# Colon.net
KiCad netlist of a schematic drawn in EAGLE
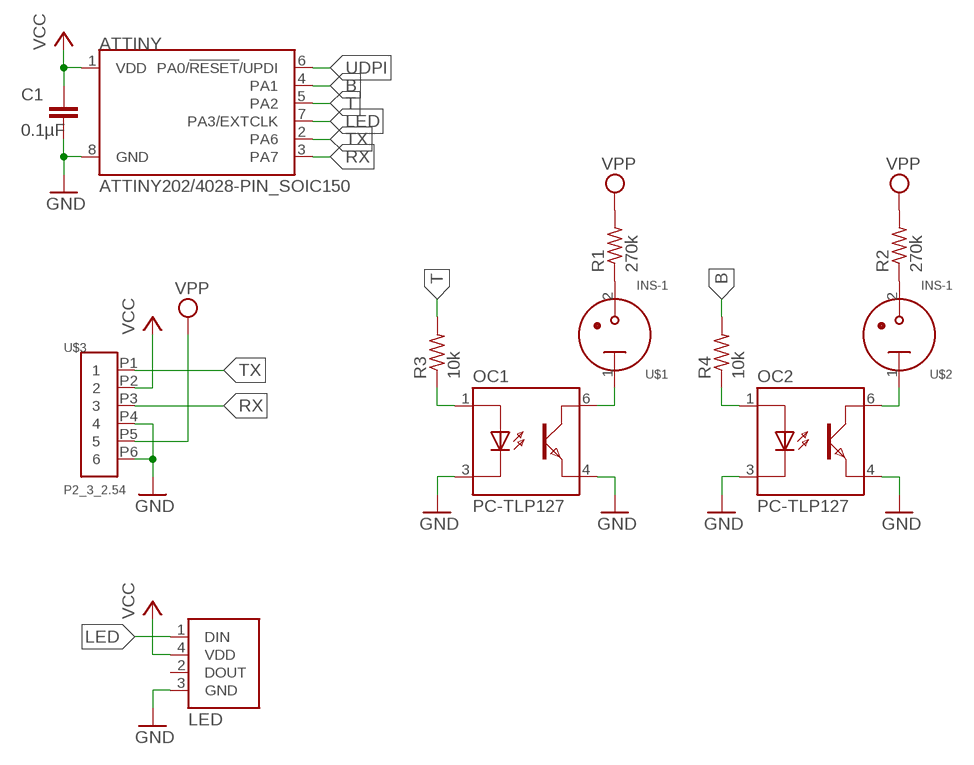
[diagram p0: schematic, sheet 1]

(export (version "E")
  (design (tool "Eeschema 10.0.6"))
  (components
    (comp (ref "ATTINY")
      (value "ATTINY202/4028-PIN_SOIC150")
      (footprint "eagle-import:SOIC127P600X175-8N")
      (libsource (lib "eagle-import") (part "ATTINY202/4028-PIN_SOIC150"))
    )
    (comp (ref "C1")
      (value "0.1µF")
      (footprint "eagle-import:C0603")
      (libsource (lib "eagle-import") (part "C-EUC0603"))
    )
    (comp (ref "LED")
      (value "SK6812SIDE")
      (footprint "eagle-import:SK6812SIDE")
      (libsource (lib "eagle-import") (part "SK6812SIDE"))
    )
    (comp (ref "OC1")
      (value "PC-TLP127")
      (footprint "eagle-import:MINIFLAT4")
      (libsource (lib "eagle-import") (part "PC-TLP127"))
    )
    (comp (ref "OC2")
      (value "PC-TLP127")
      (footprint "eagle-import:MINIFLAT4")
      (libsource (lib "eagle-import") (part "PC-TLP127"))
    )
    (comp (ref "R1")
      (value "270k")
      (footprint "eagle-import:R0603")
      (libsource (lib "eagle-import") (part "R-US_R0603"))
    )
    (comp (ref "R2")
      (value "270k")
      (footprint "eagle-import:R0603")
      (libsource (lib "eagle-import") (part "R-US_R0603"))
    )
    (comp (ref "R3")
      (value "10k")
      (footprint "eagle-import:R0603")
      (libsource (lib "eagle-import") (part "R-US_R0603"))
    )
    (comp (ref "R4")
      (value "10k")
      (footprint "eagle-import:R0603")
      (libsource (lib "eagle-import") (part "R-US_R0603"))
    )
    (comp (ref "U$1")
      (value "INS-1")
      (footprint "eagle-import:INS-1")
      (libsource (lib "eagle-import") (part "INS-1"))
    )
    (comp (ref "U$2")
      (value "INS-1")
      (footprint "eagle-import:INS-1")
      (libsource (lib "eagle-import") (part "INS-1"))
    )
    (comp (ref "U$3")
      (value "P2_3_2.54")
      (footprint "eagle-import:P2_3_2.54")
      (libsource (lib "eagle-import") (part "P2_3_2.54"))
    )
  )
  (nets
    (net (code "1") (name "B") (class "Default")
      (node (ref "ATTINY") (pin "4") (pinfunction "PA1_4") (pintype "bidirectional"))
      (node (ref "R4") (pin "2") (pinfunction "2_2") (pintype "passive"))
    )
    (net (code "2") (name "GND") (class "Default")
      (node (ref "ATTINY") (pin "8") (pinfunction "GND_8") (pintype "power_in"))
      (node (ref "C1") (pin "2") (pinfunction "2_2") (pintype "passive"))
      (node (ref "LED") (pin "3") (pinfunction "GND_3") (pintype "power_in"))
      (node (ref "OC1") (pin "3") (pinfunction "C_3") (pintype "bidirectional"))
      (node (ref "OC1") (pin "4") (pinfunction "TE_4") (pintype "bidirectional"))
      (node (ref "OC2") (pin "3") (pinfunction "C_3") (pintype "bidirectional"))
      (node (ref "OC2") (pin "4") (pinfunction "TE_4") (pintype "bidirectional"))
      (node (ref "U$3") (pin "P4") (pinfunction "4_P4") (pintype "bidirectional"))
      (node (ref "U$3") (pin "P6") (pinfunction "6_P6") (pintype "bidirectional"))
    )
    (net (code "3") (name "LED") (class "Default")
      (node (ref "ATTINY") (pin "7") (pinfunction "PA3/EXTCLK_7") (pintype "bidirectional"))
      (node (ref "LED") (pin "1") (pinfunction "DIN_1") (pintype "input"))
    )
    (net (code "4") (name "Net-(OC1-A)") (class "Default")
      (node (ref "OC1") (pin "1") (pinfunction "A_1") (pintype "bidirectional"))
      (node (ref "R3") (pin "1") (pinfunction "1_1") (pintype "passive"))
    )
    (net (code "5") (name "Net-(OC1-TC)") (class "Default")
      (node (ref "OC1") (pin "6") (pinfunction "TC_6") (pintype "bidirectional"))
      (node (ref "U$1") (pin "1") (pinfunction "A_1") (pintype "bidirectional"))
    )
    (net (code "6") (name "Net-(OC2-A)") (class "Default")
      (node (ref "OC2") (pin "1") (pinfunction "A_1") (pintype "bidirectional"))
      (node (ref "R4") (pin "1") (pinfunction "1_1") (pintype "passive"))
    )
    (net (code "7") (name "Net-(OC2-TC)") (class "Default")
      (node (ref "OC2") (pin "6") (pinfunction "TC_6") (pintype "bidirectional"))
      (node (ref "U$2") (pin "1") (pinfunction "A_1") (pintype "bidirectional"))
    )
    (net (code "8") (name "Net-(U$1-C)") (class "Default")
      (node (ref "R1") (pin "1") (pinfunction "1_1") (pintype "passive"))
      (node (ref "U$1") (pin "2") (pinfunction "C_2") (pintype "bidirectional"))
    )
    (net (code "9") (name "Net-(U$2-C)") (class "Default")
      (node (ref "R2") (pin "1") (pinfunction "1_1") (pintype "passive"))
      (node (ref "U$2") (pin "2") (pinfunction "C_2") (pintype "bidirectional"))
    )
    (net (code "10") (name "RX") (class "Default")
      (node (ref "ATTINY") (pin "3") (pinfunction "PA7_3") (pintype "bidirectional"))
      (node (ref "U$3") (pin "P3") (pinfunction "3_P3") (pintype "bidirectional"))
    )
    (net (code "11") (name "T") (class "Default")
      (node (ref "ATTINY") (pin "5") (pinfunction "PA2_5") (pintype "bidirectional"))
      (node (ref "R3") (pin "2") (pinfunction "2_2") (pintype "passive"))
    )
    (net (code "12") (name "TX") (class "Default")
      (node (ref "ATTINY") (pin "2") (pinfunction "PA6_2") (pintype "bidirectional"))
      (node (ref "U$3") (pin "P1") (pinfunction "1_P1") (pintype "bidirectional"))
    )
    (net (code "13") (name "UDPI") (class "Default")
      (node (ref "ATTINY") (pin "6") (pinfunction "PA0/~{RESET}/UPDI_6") (pintype "bidirectional"))
    )
    (net (code "14") (name "VCC") (class "Default")
      (node (ref "ATTINY") (pin "1") (pinfunction "VDD_1") (pintype "power_in"))
      (node (ref "C1") (pin "1") (pinfunction "1_1") (pintype "passive"))
      (node (ref "LED") (pin "4") (pinfunction "VDD_4") (pintype "power_in"))
      (node (ref "U$3") (pin "P2") (pinfunction "2_P2") (pintype "bidirectional"))
    )
    (net (code "15") (name "VPP") (class "Default")
      (node (ref "R1") (pin "2") (pinfunction "2_2") (pintype "passive"))
      (node (ref "R2") (pin "2") (pinfunction "2_2") (pintype "passive"))
      (node (ref "U$3") (pin "P5") (pinfunction "5_P5") (pintype "bidirectional"))
    )
    (net (code "16") (name "unconnected-(LED-DOUT-Pad2)") (class "Default")
      (node (ref "LED") (pin "2") (pinfunction "DOUT_2") (pintype "output"))
    )
  )
)
